# Debug.net
KiCad netlist of a schematic drawn in Altium Designer
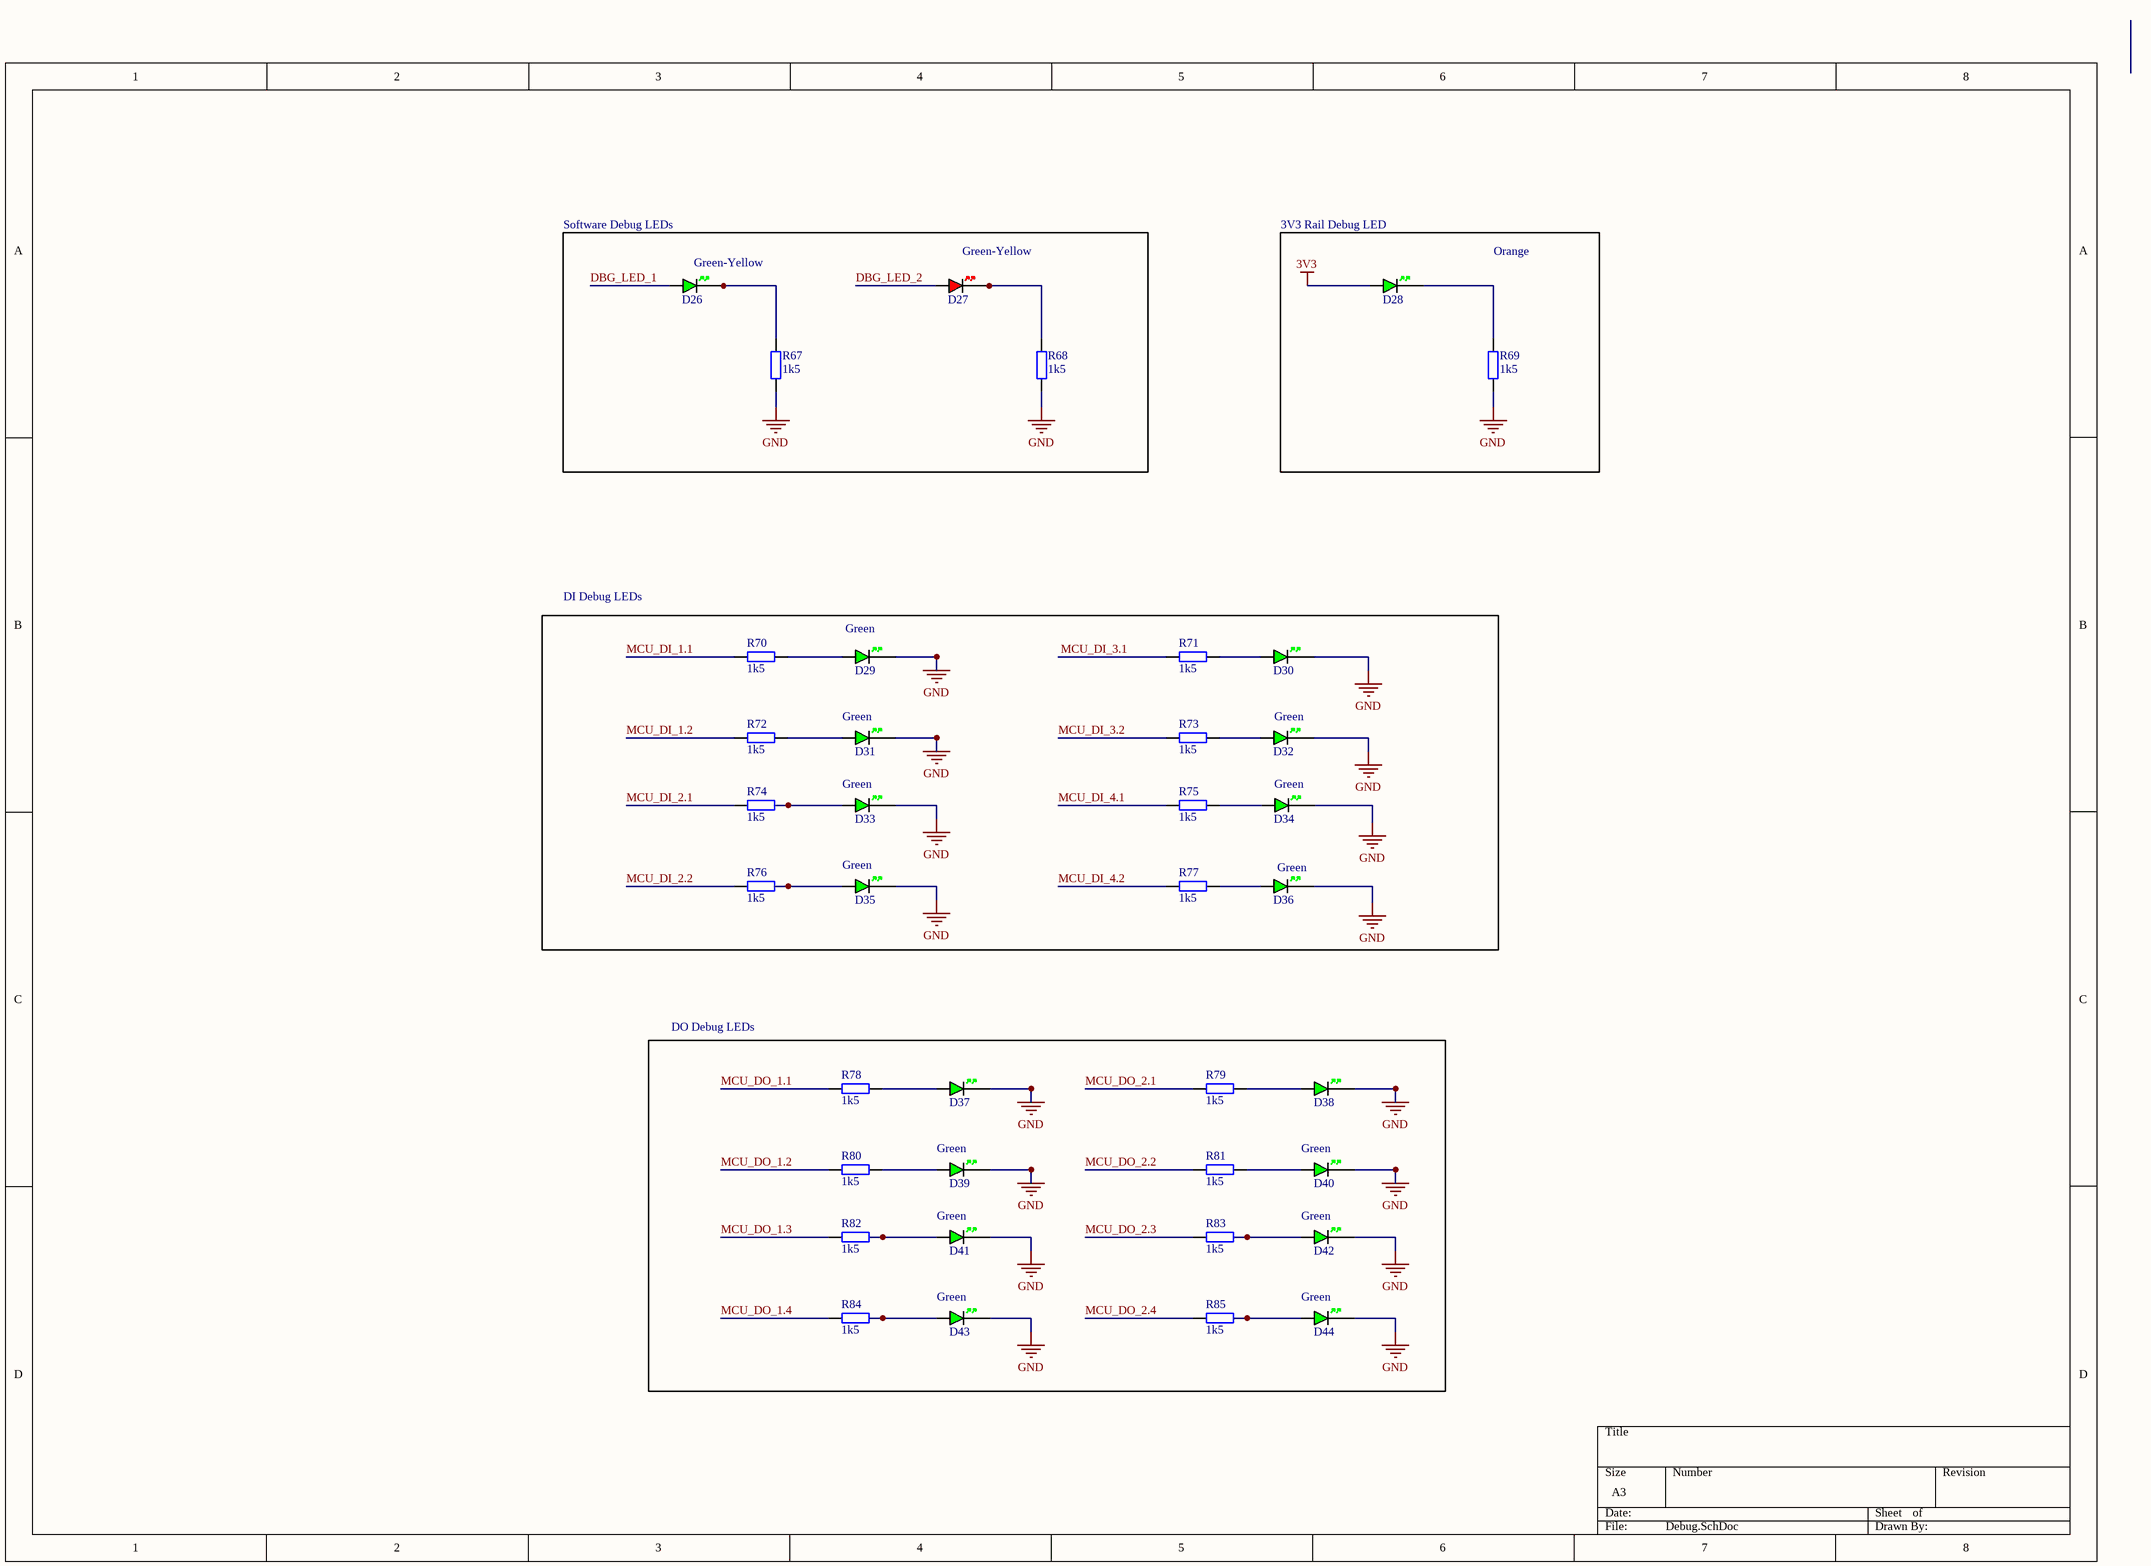
[diagram p0: Debug.SchDoc]

(export (version "E")
  (design (tool "Eeschema 10.0.6"))
  (components
    (comp (ref "D26")
      (value "GREEN")
      (footprint "LED_0402_GREEN")
      (description "LED 0402 GREEN SMD")
      (libsource (lib "Schematic-Lib-PhilsLab") (part "LED_0402_GREEN"))
    )
    (comp (ref "D27")
      (value "RED")
      (footprint "LED_0402_RED")
      (description "LED 0402 RED SMD")
      (libsource (lib "Schematic-Lib-PhilsLab") (part "LED_0402_RED"))
    )
    (comp (ref "D28")
      (value "GREEN")
      (footprint "LED_0402_GREEN")
      (description "LED 0402 GREEN SMD")
      (libsource (lib "Schematic-Lib-PhilsLab") (part "LED_0402_GREEN"))
    )
    (comp (ref "D29")
      (value "GREEN")
      (footprint "LED_0402_GREEN")
      (description "LED 0402 GREEN SMD")
      (libsource (lib "Schematic-Lib-PhilsLab") (part "LED_0402_GREEN"))
    )
    (comp (ref "D30")
      (value "GREEN")
      (footprint "LED_0402_GREEN")
      (description "LED 0402 GREEN SMD")
      (libsource (lib "Schematic-Lib-PhilsLab") (part "LED_0402_GREEN"))
    )
    (comp (ref "D31")
      (value "GREEN")
      (footprint "LED_0402_GREEN")
      (description "LED 0402 GREEN SMD")
      (libsource (lib "Schematic-Lib-PhilsLab") (part "LED_0402_GREEN"))
    )
    (comp (ref "D32")
      (value "GREEN")
      (footprint "LED_0402_GREEN")
      (description "LED 0402 GREEN SMD")
      (libsource (lib "Schematic-Lib-PhilsLab") (part "LED_0402_GREEN"))
    )
    (comp (ref "D33")
      (value "GREEN")
      (footprint "LED_0402_GREEN")
      (description "LED 0402 GREEN SMD")
      (libsource (lib "Schematic-Lib-PhilsLab") (part "LED_0402_GREEN"))
    )
    (comp (ref "D34")
      (value "GREEN")
      (footprint "LED_0402_GREEN")
      (description "LED 0402 GREEN SMD")
      (libsource (lib "Schematic-Lib-PhilsLab") (part "LED_0402_GREEN"))
    )
    (comp (ref "D35")
      (value "GREEN")
      (footprint "LED_0402_GREEN")
      (description "LED 0402 GREEN SMD")
      (libsource (lib "Schematic-Lib-PhilsLab") (part "LED_0402_GREEN"))
    )
    (comp (ref "D36")
      (value "GREEN")
      (footprint "LED_0402_GREEN")
      (description "LED 0402 GREEN SMD")
      (libsource (lib "Schematic-Lib-PhilsLab") (part "LED_0402_GREEN"))
    )
    (comp (ref "D37")
      (value "GREEN")
      (footprint "LED_0402_GREEN")
      (description "LED 0402 GREEN SMD")
      (libsource (lib "Schematic-Lib-PhilsLab") (part "LED_0402_GREEN"))
    )
    (comp (ref "D38")
      (value "GREEN")
      (footprint "LED_0402_GREEN")
      (description "LED 0402 GREEN SMD")
      (libsource (lib "Schematic-Lib-PhilsLab") (part "LED_0402_GREEN"))
    )
    (comp (ref "D39")
      (value "GREEN")
      (footprint "LED_0402_GREEN")
      (description "LED 0402 GREEN SMD")
      (libsource (lib "Schematic-Lib-PhilsLab") (part "LED_0402_GREEN"))
    )
    (comp (ref "D40")
      (value "GREEN")
      (footprint "LED_0402_GREEN")
      (description "LED 0402 GREEN SMD")
      (libsource (lib "Schematic-Lib-PhilsLab") (part "LED_0402_GREEN"))
    )
    (comp (ref "D41")
      (value "GREEN")
      (footprint "LED_0402_GREEN")
      (description "LED 0402 GREEN SMD")
      (libsource (lib "Schematic-Lib-PhilsLab") (part "LED_0402_GREEN"))
    )
    (comp (ref "D42")
      (value "GREEN")
      (footprint "LED_0402_GREEN")
      (description "LED 0402 GREEN SMD")
      (libsource (lib "Schematic-Lib-PhilsLab") (part "LED_0402_GREEN"))
    )
    (comp (ref "D43")
      (value "GREEN")
      (footprint "LED_0402_GREEN")
      (description "LED 0402 GREEN SMD")
      (libsource (lib "Schematic-Lib-PhilsLab") (part "LED_0402_GREEN"))
    )
    (comp (ref "D44")
      (value "GREEN")
      (footprint "LED_0402_GREEN")
      (description "LED 0402 GREEN SMD")
      (libsource (lib "Schematic-Lib-PhilsLab") (part "LED_0402_GREEN"))
    )
    (comp (ref "R67")
      (value "1k5")
      (footprint "RES_0402")
      (description "Resistor SMD 0402")
      (libsource (lib "Schematic-Lib-PhilsLab") (part "RES_0402"))
    )
    (comp (ref "R68")
      (value "1k5")
      (footprint "RES_0402")
      (description "Resistor SMD 0402")
      (libsource (lib "Schematic-Lib-PhilsLab") (part "RES_0402"))
    )
    (comp (ref "R69")
      (value "1k5")
      (footprint "RES_0402")
      (description "Resistor SMD 0402")
      (libsource (lib "Schematic-Lib-PhilsLab") (part "RES_0402"))
    )
    (comp (ref "R70")
      (value "1k5")
      (footprint "RES_0402")
      (description "Resistor SMD 0402")
      (libsource (lib "Schematic-Lib-PhilsLab") (part "RES_0402"))
    )
    (comp (ref "R71")
      (value "1k5")
      (footprint "RES_0402")
      (description "Resistor SMD 0402")
      (libsource (lib "Schematic-Lib-PhilsLab") (part "RES_0402"))
    )
    (comp (ref "R72")
      (value "1k5")
      (footprint "RES_0402")
      (description "Resistor SMD 0402")
      (libsource (lib "Schematic-Lib-PhilsLab") (part "RES_0402"))
    )
    (comp (ref "R73")
      (value "1k5")
      (footprint "RES_0402")
      (description "Resistor SMD 0402")
      (libsource (lib "Schematic-Lib-PhilsLab") (part "RES_0402"))
    )
    (comp (ref "R74")
      (value "1k5")
      (footprint "RES_0402")
      (description "Resistor SMD 0402")
      (libsource (lib "Schematic-Lib-PhilsLab") (part "RES_0402"))
    )
    (comp (ref "R75")
      (value "1k5")
      (footprint "RES_0402")
      (description "Resistor SMD 0402")
      (libsource (lib "Schematic-Lib-PhilsLab") (part "RES_0402"))
    )
    (comp (ref "R76")
      (value "1k5")
      (footprint "RES_0402")
      (description "Resistor SMD 0402")
      (libsource (lib "Schematic-Lib-PhilsLab") (part "RES_0402"))
    )
    (comp (ref "R77")
      (value "1k5")
      (footprint "RES_0402")
      (description "Resistor SMD 0402")
      (libsource (lib "Schematic-Lib-PhilsLab") (part "RES_0402"))
    )
    (comp (ref "R78")
      (value "1k5")
      (footprint "RES_0402")
      (description "Resistor SMD 0402")
      (libsource (lib "Schematic-Lib-PhilsLab") (part "RES_0402"))
    )
    (comp (ref "R79")
      (value "1k5")
      (footprint "RES_0402")
      (description "Resistor SMD 0402")
      (libsource (lib "Schematic-Lib-PhilsLab") (part "RES_0402"))
    )
    (comp (ref "R80")
      (value "1k5")
      (footprint "RES_0402")
      (description "Resistor SMD 0402")
      (libsource (lib "Schematic-Lib-PhilsLab") (part "RES_0402"))
    )
    (comp (ref "R81")
      (value "1k5")
      (footprint "RES_0402")
      (description "Resistor SMD 0402")
      (libsource (lib "Schematic-Lib-PhilsLab") (part "RES_0402"))
    )
    (comp (ref "R82")
      (value "1k5")
      (footprint "RES_0402")
      (description "Resistor SMD 0402")
      (libsource (lib "Schematic-Lib-PhilsLab") (part "RES_0402"))
    )
    (comp (ref "R83")
      (value "1k5")
      (footprint "RES_0402")
      (description "Resistor SMD 0402")
      (libsource (lib "Schematic-Lib-PhilsLab") (part "RES_0402"))
    )
    (comp (ref "R84")
      (value "1k5")
      (footprint "RES_0402")
      (description "Resistor SMD 0402")
      (libsource (lib "Schematic-Lib-PhilsLab") (part "RES_0402"))
    )
    (comp (ref "R85")
      (value "1k5")
      (footprint "RES_0402")
      (description "Resistor SMD 0402")
      (libsource (lib "Schematic-Lib-PhilsLab") (part "RES_0402"))
    )
  )
  (nets
    (net (code "1") (name "/DBG_LED_1") (class "Default")
      (node (ref "D26") (pin "A") (pinfunction "A_A") (pintype "passive"))
    )
    (net (code "2") (name "/DBG_LED_2") (class "Default")
      (node (ref "D27") (pin "A") (pinfunction "A_A") (pintype "passive"))
    )
    (net (code "3") (name "/MCU_DI_1.1") (class "Default")
      (node (ref "R70") (pin "2") (pinfunction "2_2") (pintype "passive"))
    )
    (net (code "4") (name "/MCU_DI_1.2") (class "Default")
      (node (ref "R72") (pin "2") (pinfunction "2_2") (pintype "passive"))
    )
    (net (code "5") (name "/MCU_DI_2.1") (class "Default")
      (node (ref "R74") (pin "2") (pinfunction "2_2") (pintype "passive"))
    )
    (net (code "6") (name "/MCU_DI_2.2") (class "Default")
      (node (ref "R76") (pin "2") (pinfunction "2_2") (pintype "passive"))
    )
    (net (code "7") (name "/MCU_DI_3.1") (class "Default")
      (node (ref "R71") (pin "2") (pinfunction "2_2") (pintype "passive"))
    )
    (net (code "8") (name "/MCU_DI_3.2") (class "Default")
      (node (ref "R73") (pin "2") (pinfunction "2_2") (pintype "passive"))
    )
    (net (code "9") (name "/MCU_DI_4.1") (class "Default")
      (node (ref "R75") (pin "2") (pinfunction "2_2") (pintype "passive"))
    )
    (net (code "10") (name "/MCU_DI_4.2") (class "Default")
      (node (ref "R77") (pin "2") (pinfunction "2_2") (pintype "passive"))
    )
    (net (code "11") (name "/MCU_DO_1.1") (class "Default")
      (node (ref "R78") (pin "2") (pinfunction "2_2") (pintype "passive"))
    )
    (net (code "12") (name "/MCU_DO_1.2") (class "Default")
      (node (ref "R80") (pin "2") (pinfunction "2_2") (pintype "passive"))
    )
    (net (code "13") (name "/MCU_DO_1.3") (class "Default")
      (node (ref "R82") (pin "2") (pinfunction "2_2") (pintype "passive"))
    )
    (net (code "14") (name "/MCU_DO_1.4") (class "Default")
      (node (ref "R84") (pin "2") (pinfunction "2_2") (pintype "passive"))
    )
    (net (code "15") (name "/MCU_DO_2.1") (class "Default")
      (node (ref "R79") (pin "2") (pinfunction "2_2") (pintype "passive"))
    )
    (net (code "16") (name "/MCU_DO_2.2") (class "Default")
      (node (ref "R81") (pin "2") (pinfunction "2_2") (pintype "passive"))
    )
    (net (code "17") (name "/MCU_DO_2.3") (class "Default")
      (node (ref "R83") (pin "2") (pinfunction "2_2") (pintype "passive"))
    )
    (net (code "18") (name "/MCU_DO_2.4") (class "Default")
      (node (ref "R85") (pin "2") (pinfunction "2_2") (pintype "passive"))
    )
    (net (code "19") (name "3V3") (class "Default")
      (node (ref "D28") (pin "A") (pinfunction "A_A") (pintype "passive"))
    )
    (net (code "20") (name "GND") (class "Default")
      (node (ref "D29") (pin "K") (pinfunction "K_K") (pintype "passive"))
      (node (ref "D30") (pin "K") (pinfunction "K_K") (pintype "passive"))
      (node (ref "D31") (pin "K") (pinfunction "K_K") (pintype "passive"))
      (node (ref "D32") (pin "K") (pinfunction "K_K") (pintype "passive"))
      (node (ref "D33") (pin "K") (pinfunction "K_K") (pintype "passive"))
      (node (ref "D34") (pin "K") (pinfunction "K_K") (pintype "passive"))
      (node (ref "D35") (pin "K") (pinfunction "K_K") (pintype "passive"))
      (node (ref "D36") (pin "K") (pinfunction "K_K") (pintype "passive"))
      (node (ref "D37") (pin "K") (pinfunction "K_K") (pintype "passive"))
      (node (ref "D38") (pin "K") (pinfunction "K_K") (pintype "passive"))
      (node (ref "D39") (pin "K") (pinfunction "K_K") (pintype "passive"))
      (node (ref "D40") (pin "K") (pinfunction "K_K") (pintype "passive"))
      (node (ref "D41") (pin "K") (pinfunction "K_K") (pintype "passive"))
      (node (ref "D42") (pin "K") (pinfunction "K_K") (pintype "passive"))
      (node (ref "D43") (pin "K") (pinfunction "K_K") (pintype "passive"))
      (node (ref "D44") (pin "K") (pinfunction "K_K") (pintype "passive"))
      (node (ref "R67") (pin "1") (pinfunction "1_1") (pintype "passive"))
      (node (ref "R68") (pin "1") (pinfunction "1_1") (pintype "passive"))
      (node (ref "R69") (pin "1") (pinfunction "1_1") (pintype "passive"))
    )
    (net (code "21") (name "Net-(D26-PadK)") (class "Default")
      (node (ref "D26") (pin "K") (pinfunction "K_K") (pintype "passive"))
      (node (ref "R67") (pin "2") (pinfunction "2_2") (pintype "passive"))
    )
    (net (code "22") (name "Net-(D27-PadK)") (class "Default")
      (node (ref "D27") (pin "K") (pinfunction "K_K") (pintype "passive"))
      (node (ref "R68") (pin "2") (pinfunction "2_2") (pintype "passive"))
    )
    (net (code "23") (name "Net-(D28-PadK)") (class "Default")
      (node (ref "D28") (pin "K") (pinfunction "K_K") (pintype "passive"))
      (node (ref "R69") (pin "2") (pinfunction "2_2") (pintype "passive"))
    )
    (net (code "24") (name "Net-(D29-PadA)") (class "Default")
      (node (ref "D29") (pin "A") (pinfunction "A_A") (pintype "passive"))
      (node (ref "R70") (pin "1") (pinfunction "1_1") (pintype "passive"))
    )
    (net (code "25") (name "Net-(D30-PadA)") (class "Default")
      (node (ref "D30") (pin "A") (pinfunction "A_A") (pintype "passive"))
      (node (ref "R71") (pin "1") (pinfunction "1_1") (pintype "passive"))
    )
    (net (code "26") (name "Net-(D31-PadA)") (class "Default")
      (node (ref "D31") (pin "A") (pinfunction "A_A") (pintype "passive"))
      (node (ref "R72") (pin "1") (pinfunction "1_1") (pintype "passive"))
    )
    (net (code "27") (name "Net-(D32-PadA)") (class "Default")
      (node (ref "D32") (pin "A") (pinfunction "A_A") (pintype "passive"))
      (node (ref "R73") (pin "1") (pinfunction "1_1") (pintype "passive"))
    )
    (net (code "28") (name "Net-(D33-PadA)") (class "Default")
      (node (ref "D33") (pin "A") (pinfunction "A_A") (pintype "passive"))
      (node (ref "R74") (pin "1") (pinfunction "1_1") (pintype "passive"))
    )
    (net (code "29") (name "Net-(D34-PadA)") (class "Default")
      (node (ref "D34") (pin "A") (pinfunction "A_A") (pintype "passive"))
      (node (ref "R75") (pin "1") (pinfunction "1_1") (pintype "passive"))
    )
    (net (code "30") (name "Net-(D35-PadA)") (class "Default")
      (node (ref "D35") (pin "A") (pinfunction "A_A") (pintype "passive"))
      (node (ref "R76") (pin "1") (pinfunction "1_1") (pintype "passive"))
    )
    (net (code "31") (name "Net-(D36-PadA)") (class "Default")
      (node (ref "D36") (pin "A") (pinfunction "A_A") (pintype "passive"))
      (node (ref "R77") (pin "1") (pinfunction "1_1") (pintype "passive"))
    )
    (net (code "32") (name "Net-(D37-PadA)") (class "Default")
      (node (ref "D37") (pin "A") (pinfunction "A_A") (pintype "passive"))
      (node (ref "R78") (pin "1") (pinfunction "1_1") (pintype "passive"))
    )
    (net (code "33") (name "Net-(D38-PadA)") (class "Default")
      (node (ref "D38") (pin "A") (pinfunction "A_A") (pintype "passive"))
      (node (ref "R79") (pin "1") (pinfunction "1_1") (pintype "passive"))
    )
    (net (code "34") (name "Net-(D39-PadA)") (class "Default")
      (node (ref "D39") (pin "A") (pinfunction "A_A") (pintype "passive"))
      (node (ref "R80") (pin "1") (pinfunction "1_1") (pintype "passive"))
    )
    (net (code "35") (name "Net-(D40-PadA)") (class "Default")
      (node (ref "D40") (pin "A") (pinfunction "A_A") (pintype "passive"))
      (node (ref "R81") (pin "1") (pinfunction "1_1") (pintype "passive"))
    )
    (net (code "36") (name "Net-(D41-PadA)") (class "Default")
      (node (ref "D41") (pin "A") (pinfunction "A_A") (pintype "passive"))
      (node (ref "R82") (pin "1") (pinfunction "1_1") (pintype "passive"))
    )
    (net (code "37") (name "Net-(D42-PadA)") (class "Default")
      (node (ref "D42") (pin "A") (pinfunction "A_A") (pintype "passive"))
      (node (ref "R83") (pin "1") (pinfunction "1_1") (pintype "passive"))
    )
    (net (code "38") (name "Net-(D43-PadA)") (class "Default")
      (node (ref "D43") (pin "A") (pinfunction "A_A") (pintype "passive"))
      (node (ref "R84") (pin "1") (pinfunction "1_1") (pintype "passive"))
    )
    (net (code "39") (name "Net-(D44-PadA)") (class "Default")
      (node (ref "D44") (pin "A") (pinfunction "A_A") (pintype "passive"))
      (node (ref "R85") (pin "1") (pinfunction "1_1") (pintype "passive"))
    )
  )
)
